# SIM_sniffer.net
KiCad netlist of a schematic drawn in EAGLE
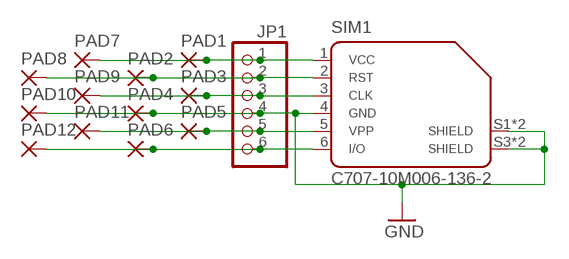
[diagram p0: schematic, sheet 1]

(export (version "E")
  (design (tool "Eeschema 10.0.6"))
  (components
    (comp (ref "JP1")
      (value "PINHD-1X6")
      (footprint "eagle-import:1X06")
      (libsource (lib "eagle-import") (part "PINHD-1X6"))
    )
    (comp (ref "PAD1")
      (value "SMD2")
      (footprint "eagle-import:SMD1,27-2,54")
      (libsource (lib "eagle-import") (part "SMD2"))
    )
    (comp (ref "PAD2")
      (value "SMD2")
      (footprint "eagle-import:SMD1,27-2,54")
      (libsource (lib "eagle-import") (part "SMD2"))
    )
    (comp (ref "PAD3")
      (value "SMD2")
      (footprint "eagle-import:SMD1,27-2,54")
      (libsource (lib "eagle-import") (part "SMD2"))
    )
    (comp (ref "PAD4")
      (value "SMD2")
      (footprint "eagle-import:SMD1,27-2,54")
      (libsource (lib "eagle-import") (part "SMD2"))
    )
    (comp (ref "PAD5")
      (value "SMD2")
      (footprint "eagle-import:SMD1,27-2,54")
      (libsource (lib "eagle-import") (part "SMD2"))
    )
    (comp (ref "PAD6")
      (value "SMD2")
      (footprint "eagle-import:SMD1,27-2,54")
      (libsource (lib "eagle-import") (part "SMD2"))
    )
    (comp (ref "PAD7")
      (value "SMD2")
      (footprint "eagle-import:SMD1,27-2,54")
      (libsource (lib "eagle-import") (part "SMD2"))
    )
    (comp (ref "PAD8")
      (value "SMD2")
      (footprint "eagle-import:SMD1,27-2,54")
      (libsource (lib "eagle-import") (part "SMD2"))
    )
    (comp (ref "PAD9")
      (value "SMD2")
      (footprint "eagle-import:SMD1,27-2,54")
      (libsource (lib "eagle-import") (part "SMD2"))
    )
    (comp (ref "PAD10")
      (value "SMD2")
      (footprint "eagle-import:SMD1,27-2,54")
      (libsource (lib "eagle-import") (part "SMD2"))
    )
    (comp (ref "PAD11")
      (value "SMD2")
      (footprint "eagle-import:SMD1,27-2,54")
      (libsource (lib "eagle-import") (part "SMD2"))
    )
    (comp (ref "PAD12")
      (value "SMD2")
      (footprint "eagle-import:SMD1,27-2,54")
      (libsource (lib "eagle-import") (part "SMD2"))
    )
    (comp (ref "SIM1")
      (value "C707-10M006-136-2")
      (footprint "eagle-import:C707_10M006_136_2")
      (libsource (lib "eagle-import") (part "C707-10M006-136-2"))
    )
  )
  (nets
    (net (code "1") (name "GND") (class "Default")
      (node (ref "JP1") (pin "4") (pinfunction "4_4") (pintype "passive"))
      (node (ref "PAD10") (pin "1") (pinfunction "P_1") (pintype "passive"))
      (node (ref "PAD4") (pin "1") (pinfunction "P_1") (pintype "passive"))
      (node (ref "SIM1") (pin "4") (pinfunction "4_4") (pintype "passive"))
      (node (ref "SIM1") (pin "S1") (pinfunction "S1_S1") (pintype "passive"))
      (node (ref "SIM1") (pin "S2") (pinfunction "S1_S2") (pintype "passive"))
      (node (ref "SIM1") (pin "S3") (pinfunction "S2_S3") (pintype "passive"))
      (node (ref "SIM1") (pin "S4") (pinfunction "S2_S4") (pintype "passive"))
    )
    (net (code "2") (name "Net-(PAD1-P)") (class "Default")
      (node (ref "JP1") (pin "1") (pinfunction "1_1") (pintype "passive"))
      (node (ref "PAD1") (pin "1") (pinfunction "P_1") (pintype "passive"))
      (node (ref "PAD7") (pin "1") (pinfunction "P_1") (pintype "passive"))
      (node (ref "SIM1") (pin "1") (pinfunction "1_1") (pintype "passive"))
    )
    (net (code "3") (name "Net-(PAD2-P)") (class "Default")
      (node (ref "JP1") (pin "2") (pinfunction "2_2") (pintype "passive"))
      (node (ref "PAD2") (pin "1") (pinfunction "P_1") (pintype "passive"))
      (node (ref "PAD8") (pin "1") (pinfunction "P_1") (pintype "passive"))
      (node (ref "SIM1") (pin "2") (pinfunction "2_2") (pintype "passive"))
    )
    (net (code "4") (name "Net-(PAD3-P)") (class "Default")
      (node (ref "JP1") (pin "3") (pinfunction "3_3") (pintype "passive"))
      (node (ref "PAD3") (pin "1") (pinfunction "P_1") (pintype "passive"))
      (node (ref "PAD9") (pin "1") (pinfunction "P_1") (pintype "passive"))
      (node (ref "SIM1") (pin "3") (pinfunction "3_3") (pintype "passive"))
    )
    (net (code "5") (name "Net-(PAD11-P)") (class "Default")
      (node (ref "JP1") (pin "5") (pinfunction "5_5") (pintype "passive"))
      (node (ref "PAD11") (pin "1") (pinfunction "P_1") (pintype "passive"))
      (node (ref "PAD5") (pin "1") (pinfunction "P_1") (pintype "passive"))
      (node (ref "SIM1") (pin "5") (pinfunction "5_5") (pintype "passive"))
    )
    (net (code "6") (name "Net-(PAD12-P)") (class "Default")
      (node (ref "JP1") (pin "6") (pinfunction "6_6") (pintype "passive"))
      (node (ref "PAD12") (pin "1") (pinfunction "P_1") (pintype "passive"))
      (node (ref "PAD6") (pin "1") (pinfunction "P_1") (pintype "passive"))
      (node (ref "SIM1") (pin "6") (pinfunction "6_6") (pintype "passive"))
    )
  )
)
